# Mergen_Ground_Station_V2_0.net
KiCad netlist of a schematic drawn in EAGLE
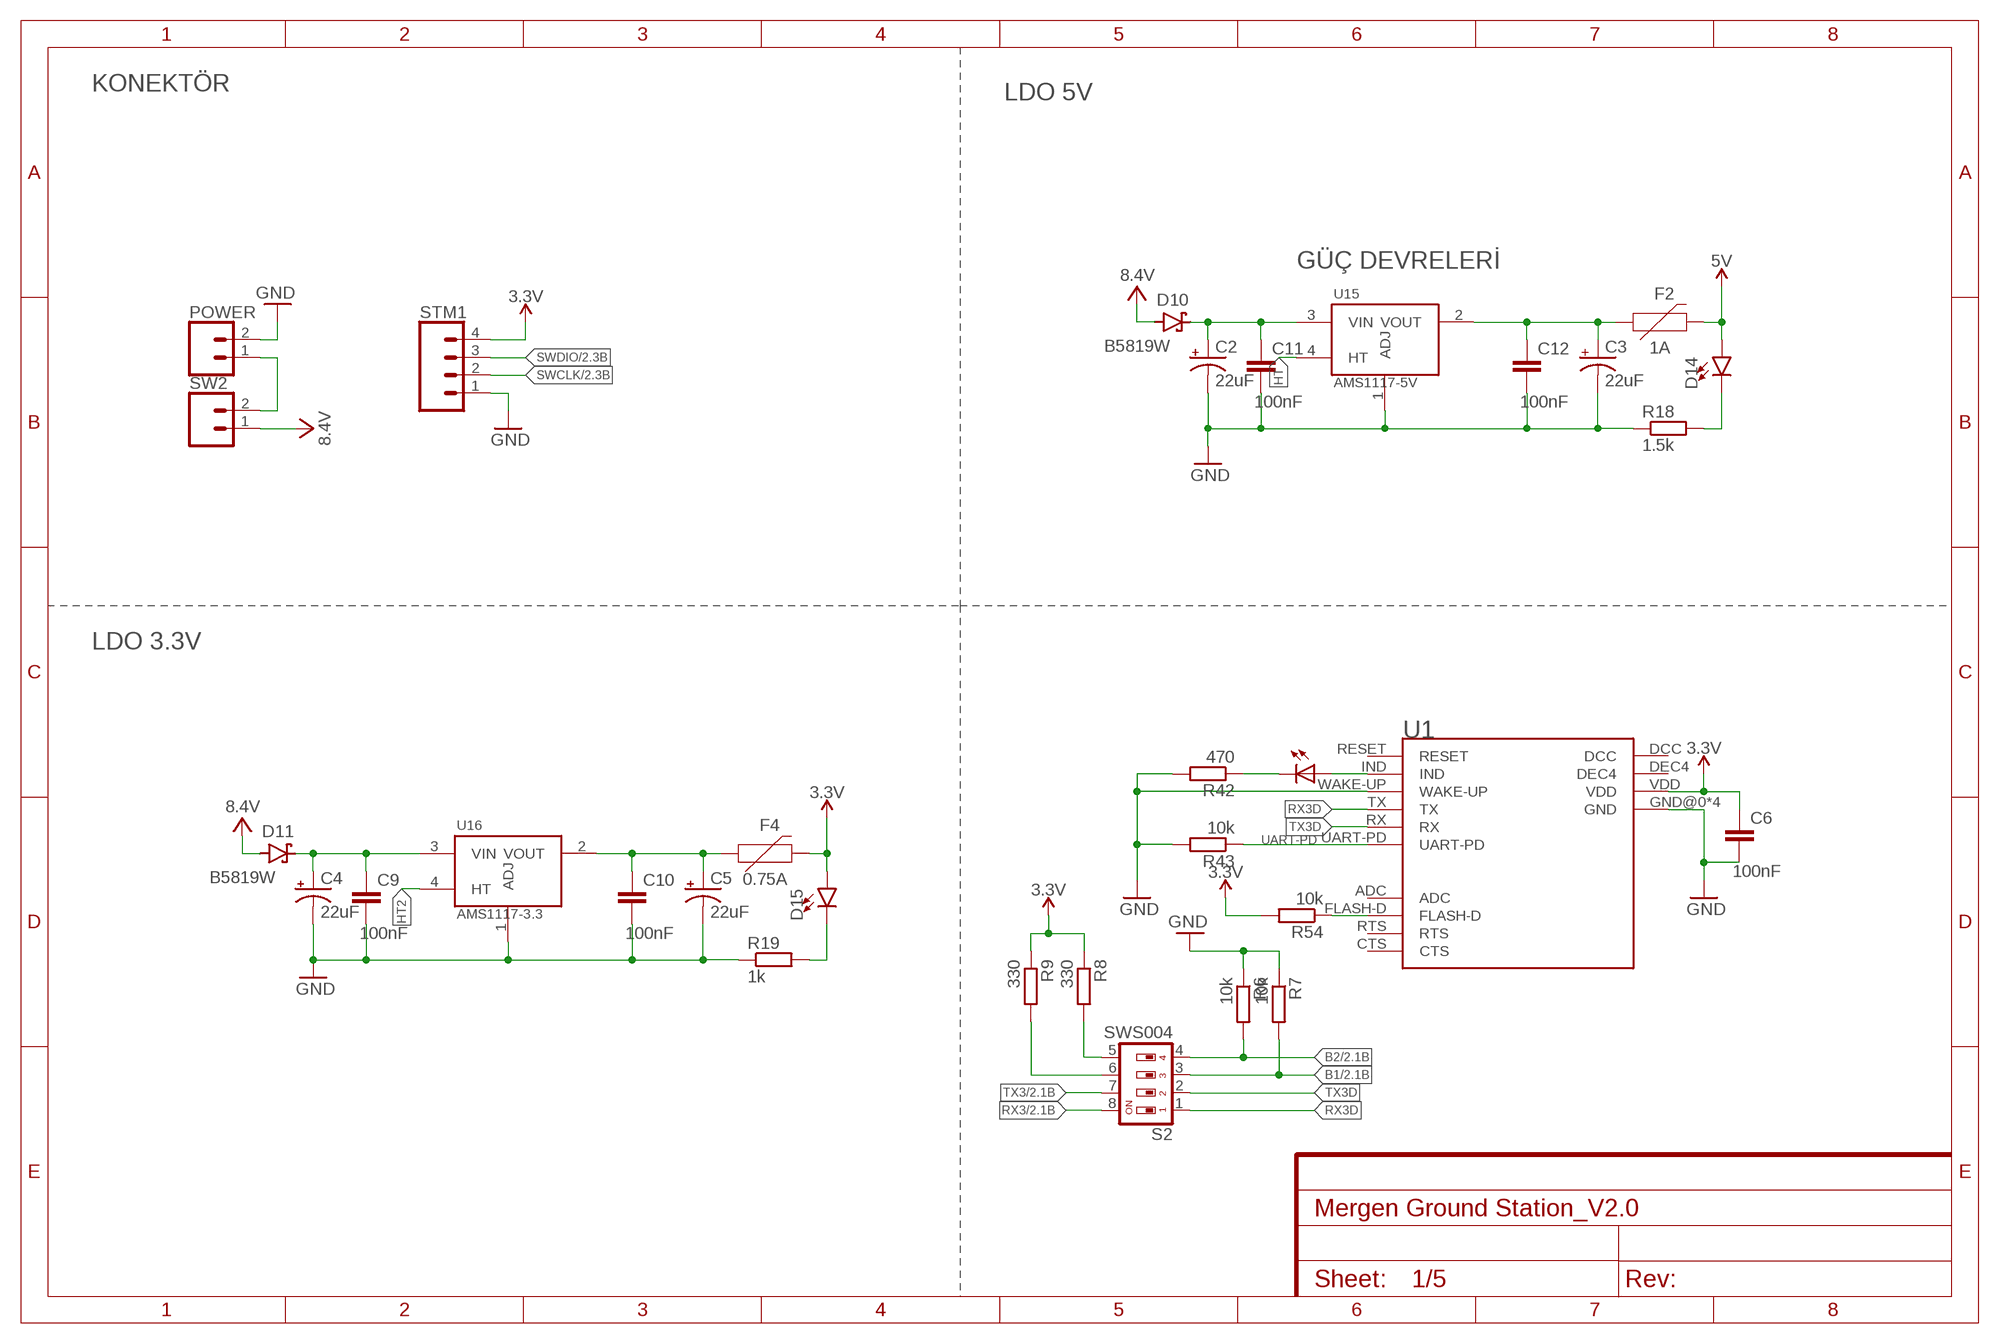
[diagram p0: schematic, sheet 1]
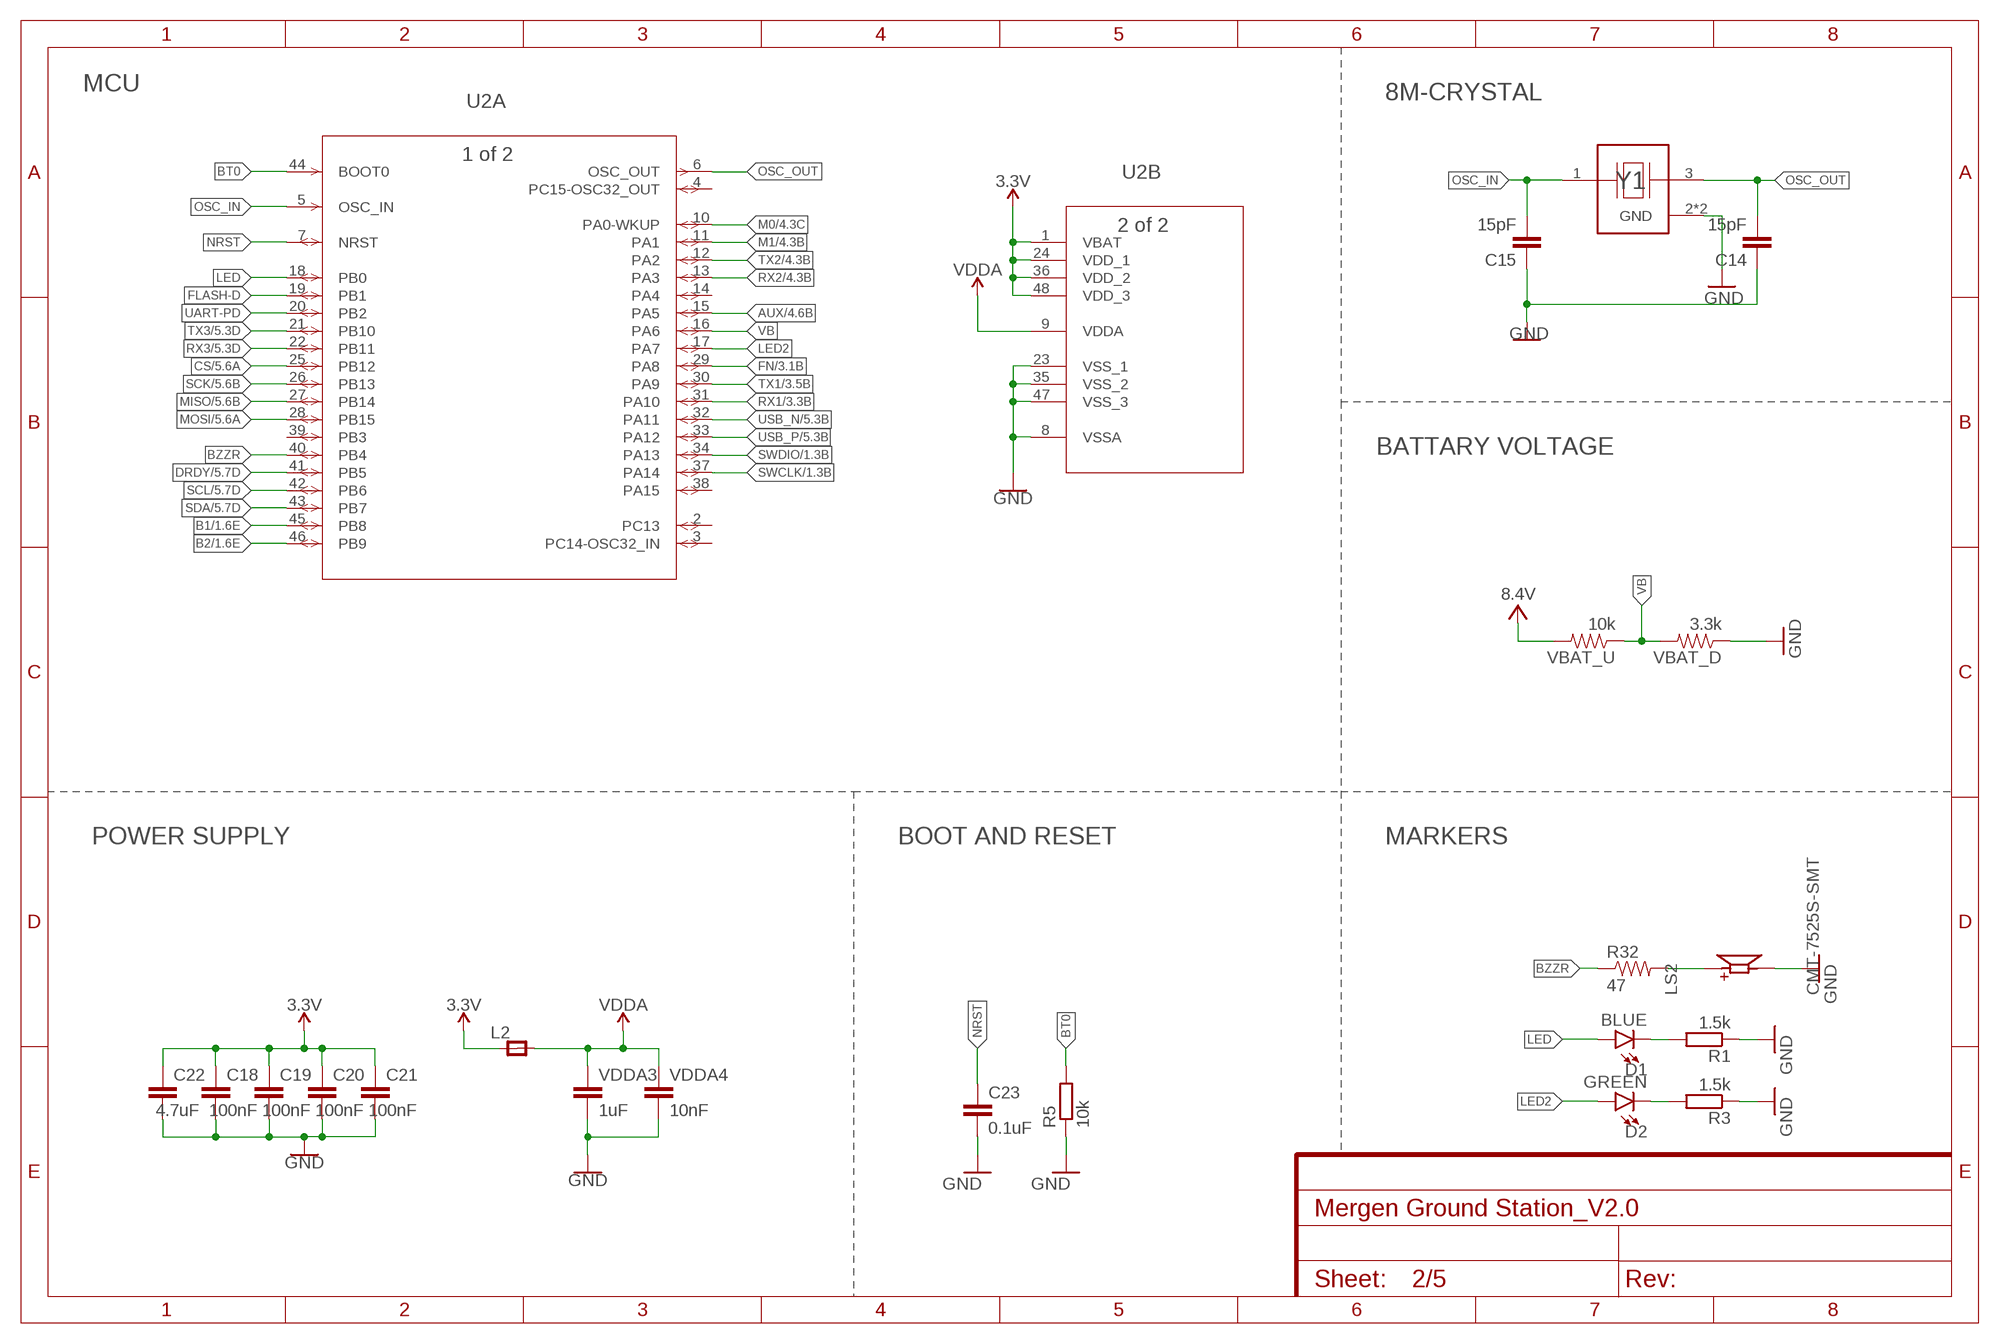
[diagram p1: schematic, sheet 2]
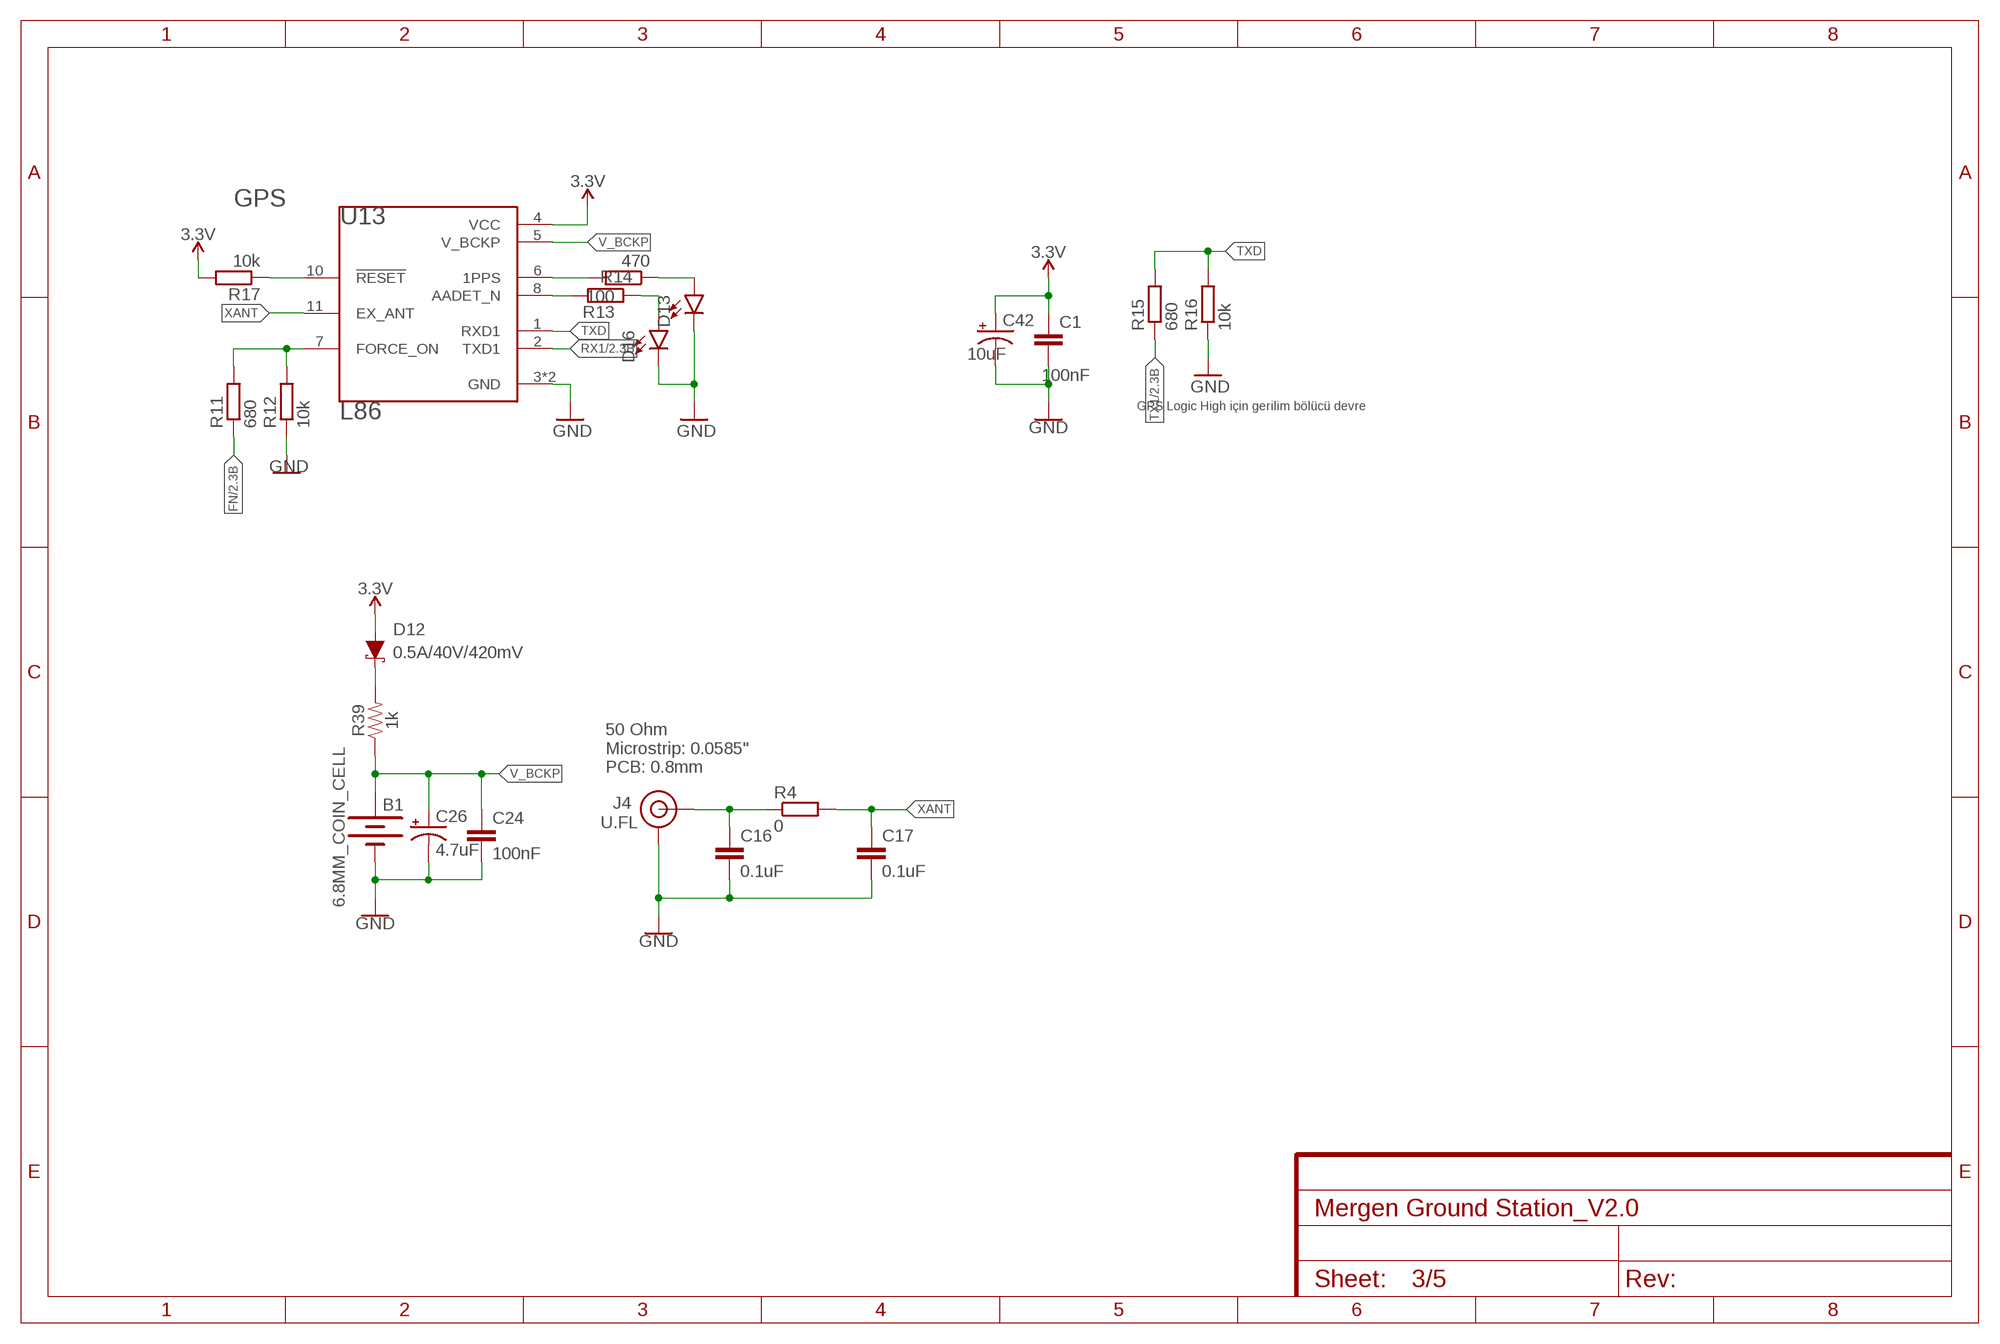
[diagram p2: schematic, sheet 3]
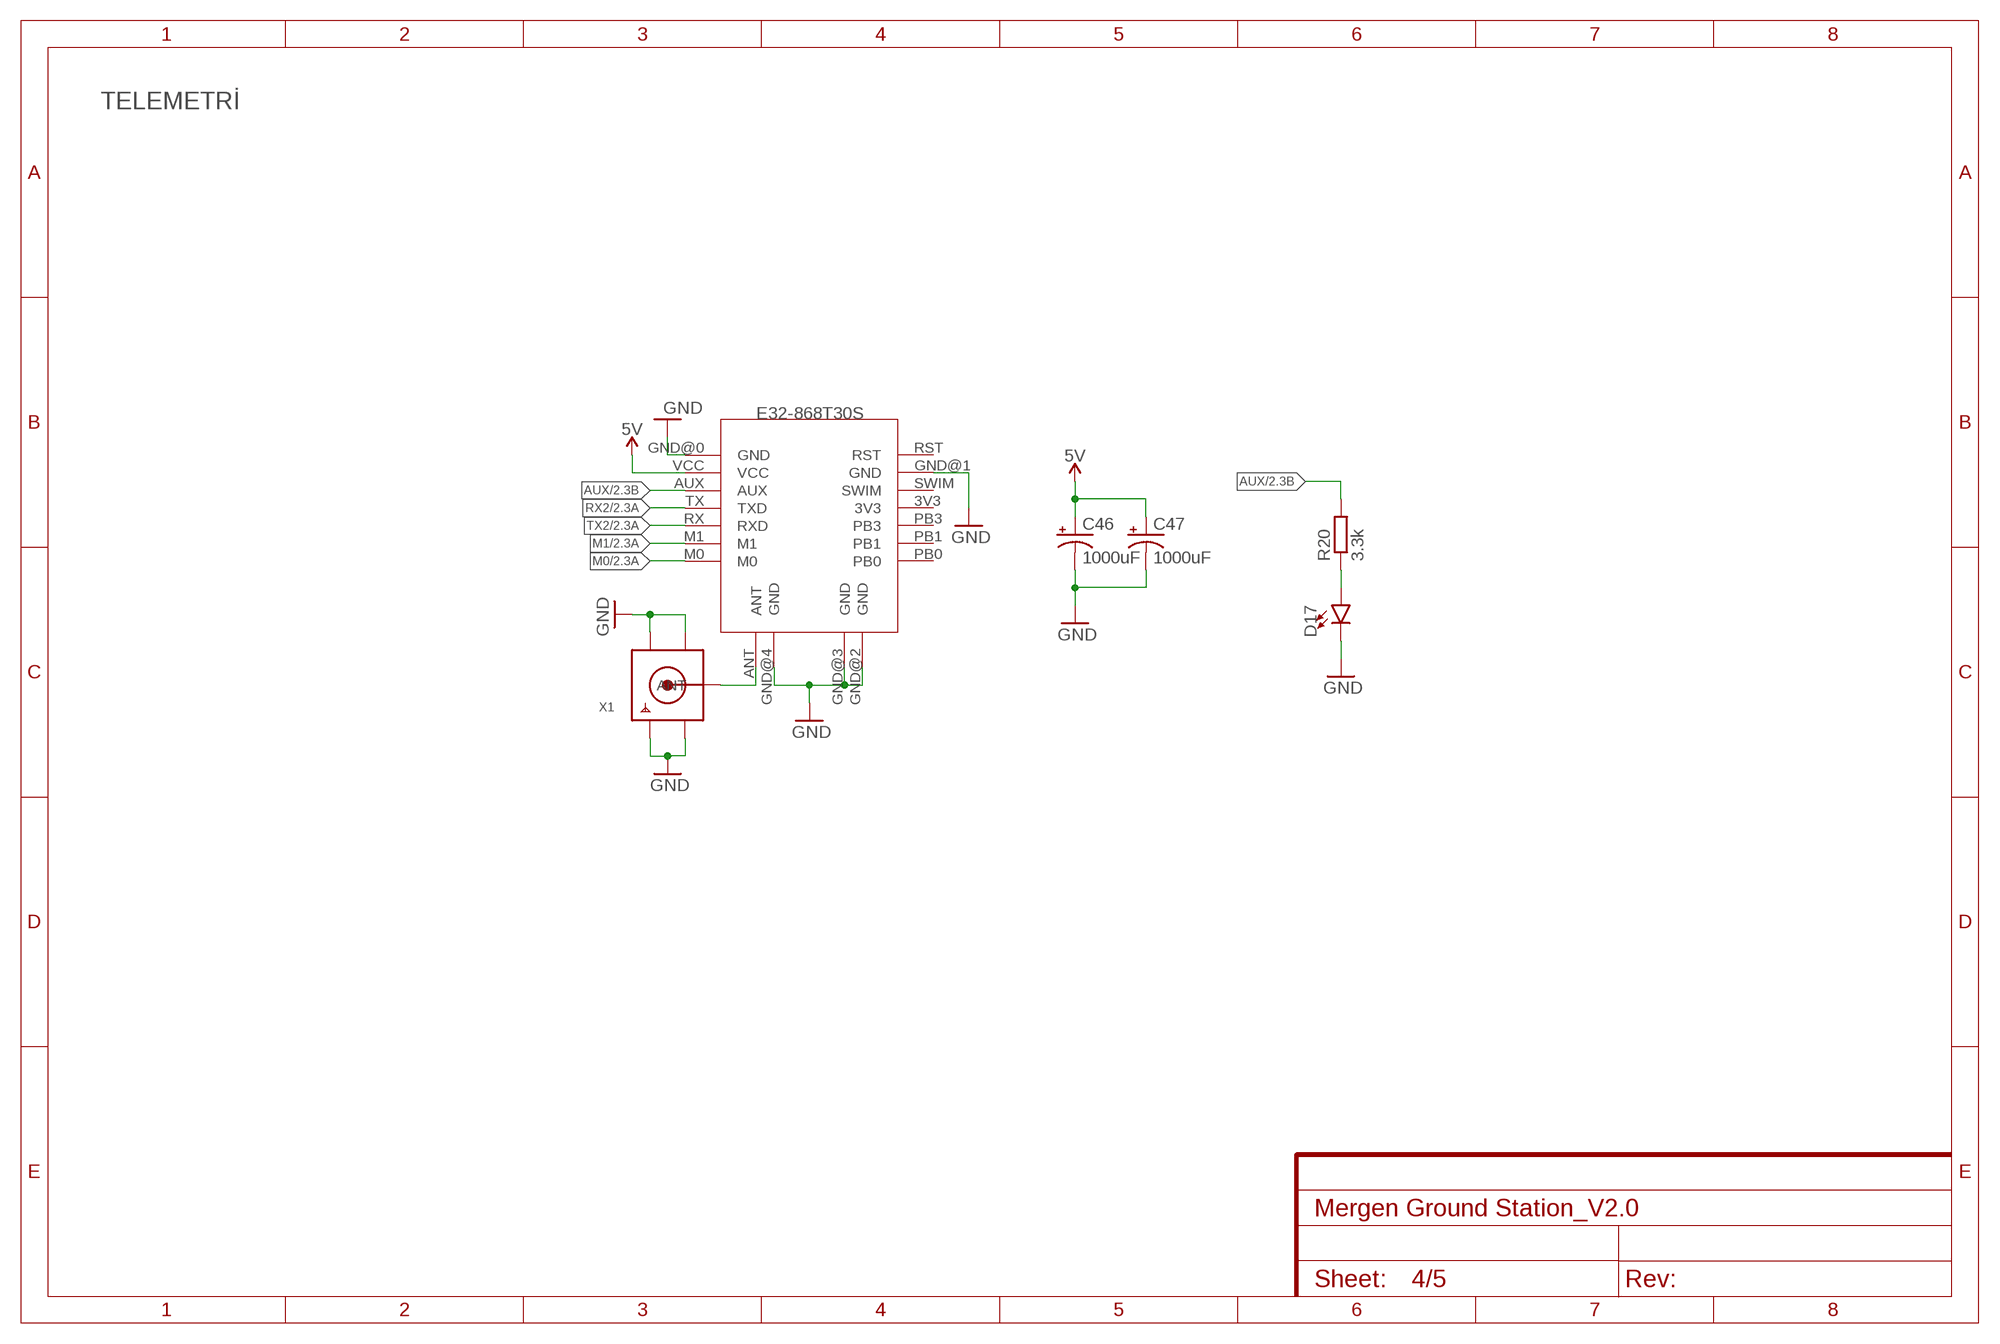
[diagram p3: schematic, sheet 4]
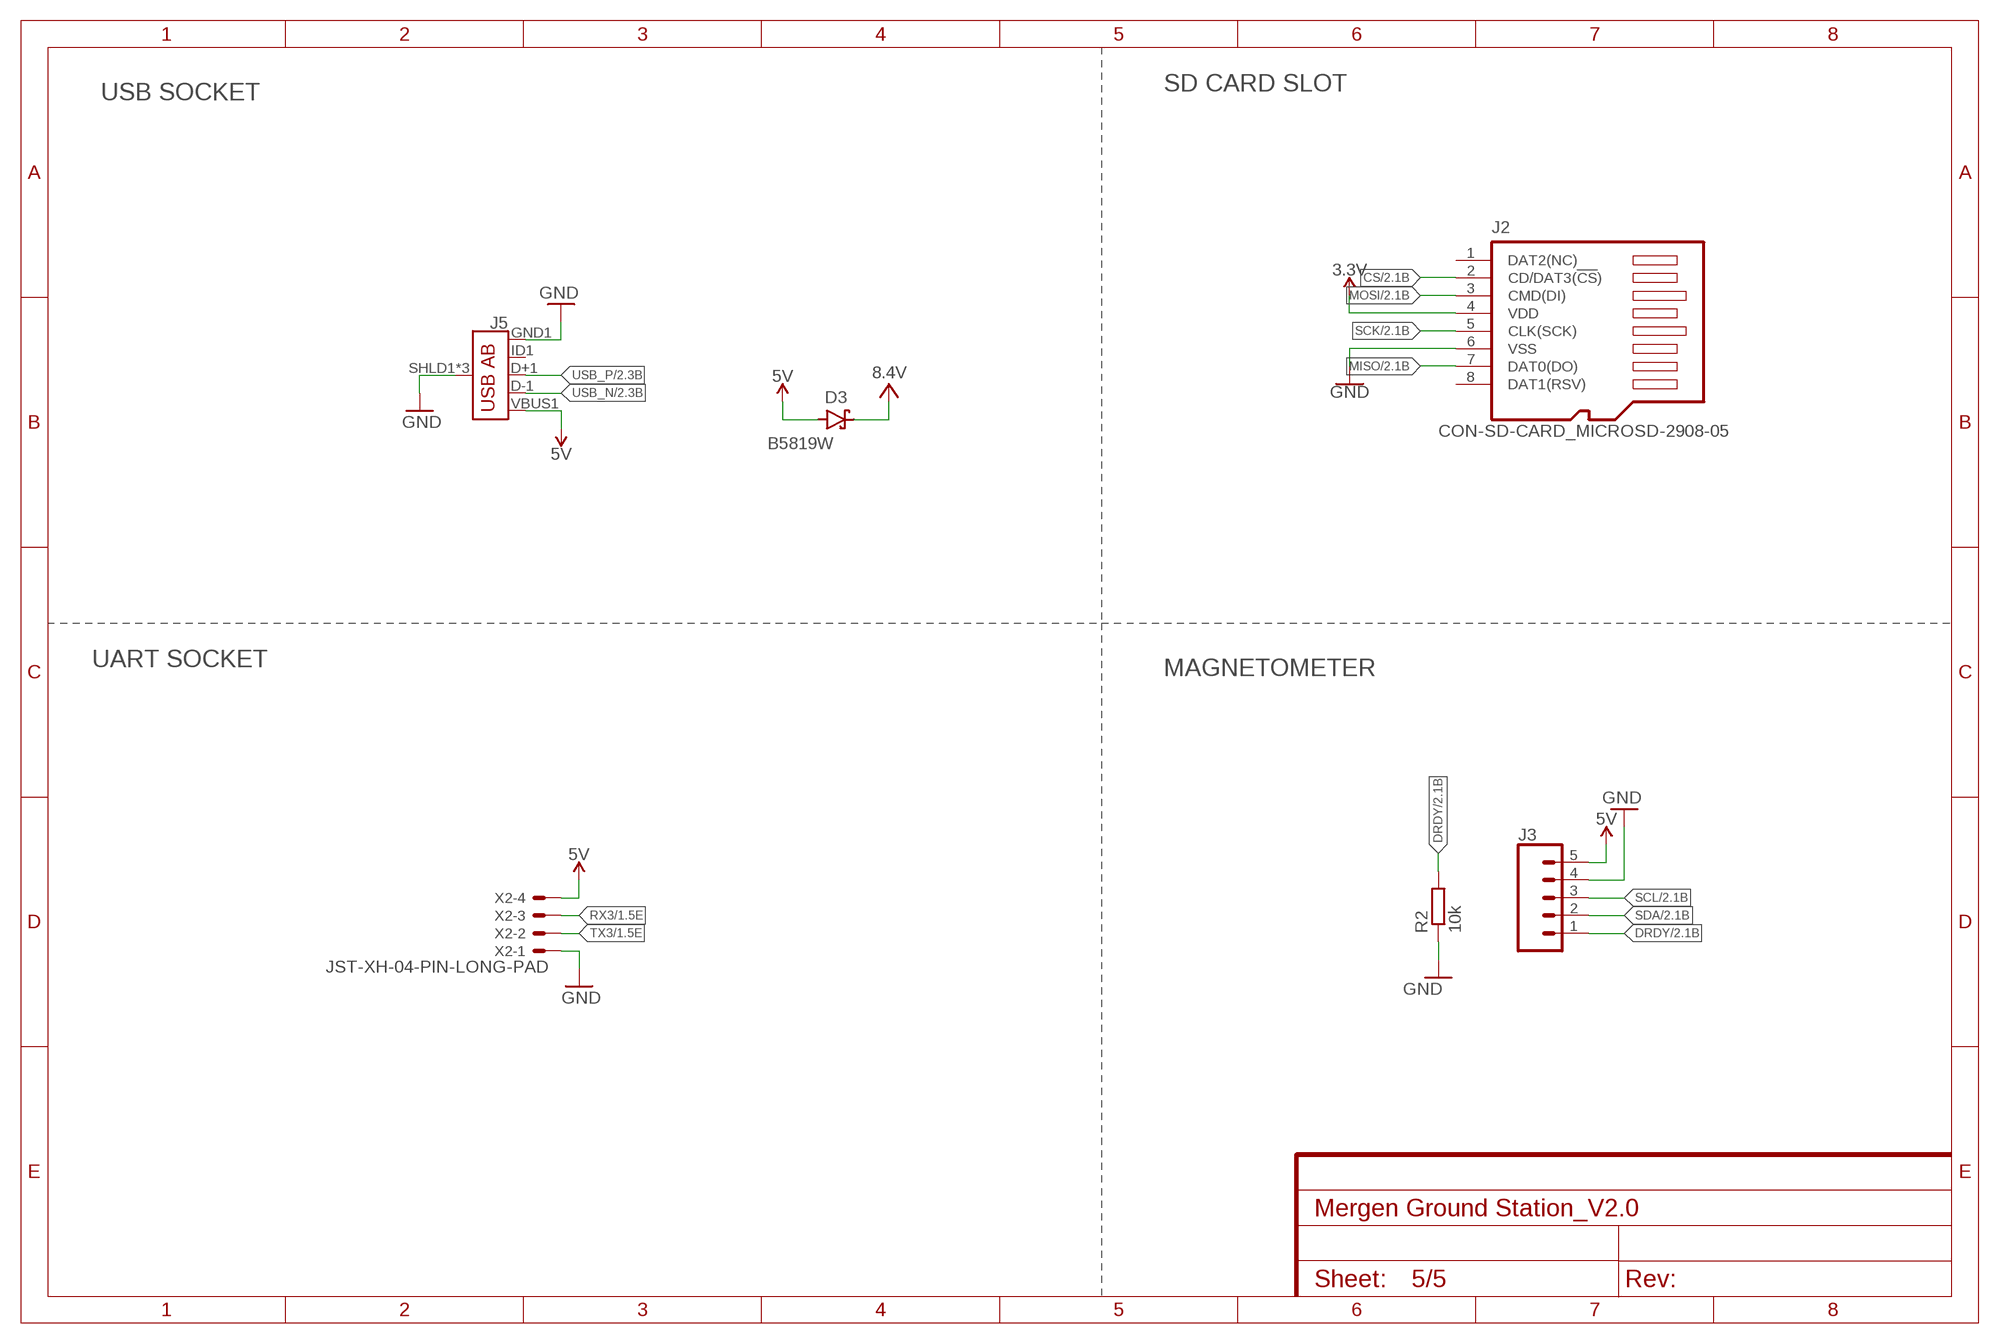
[diagram p4: schematic, sheet 5]

(export (version "E")
  (design (tool "Eeschema 10.0.6"))
  (components
    (comp (ref "C46")
      (value "1000uF")
      (footprint "eagle-import:150CLZ-1010")
      (libsource (lib "eagle-import") (part "CPOL-US150CLZ-1010"))
    )
    (comp (ref "C47")
      (value "1000uF")
      (footprint "eagle-import:150CLZ-1010")
      (libsource (lib "eagle-import") (part "CPOL-US150CLZ-1010"))
    )
    (comp (ref "D17")
      (value "LED0603")
      (footprint "eagle-import:LED-0603")
      (libsource (lib "eagle-import") (part "LED0603"))
    )
    (comp (ref "R20")
      (value "3.3k")
      (footprint "eagle-import:R0603")
      (libsource (lib "eagle-import") (part "rcl_334_R-EU_R0603"))
    )
    (comp (ref "U14")
      (value "E32-868T30S")
      (footprint "eagle-import:E32-868T30S")
      (libsource (lib "eagle-import") (part "E32-868T30S"))
    )
    (comp (ref "X1")
      (value "SMACONNECTOR")
      (footprint "eagle-import:SMA90_DIP")
      (libsource (lib "eagle-import") (part "SMACONNECTOR"))
    )
    (comp (ref "C2")
      (value "22uF")
      (footprint "eagle-import:CT3528")
      (libsource (lib "eagle-import") (part "rcl_334_CPOL-USCT3528"))
    )
    (comp (ref "C3")
      (value "22uF")
      (footprint "eagle-import:CT3528")
      (libsource (lib "eagle-import") (part "rcl_334_CPOL-USCT3528"))
    )
    (comp (ref "C4")
      (value "22uF")
      (footprint "eagle-import:CT3528")
      (libsource (lib "eagle-import") (part "rcl_334_CPOL-USCT3528"))
    )
    (comp (ref "C5")
      (value "22uF")
      (footprint "eagle-import:CT3528")
      (libsource (lib "eagle-import") (part "rcl_334_CPOL-USCT3528"))
    )
    (comp (ref "C6")
      (value "100nF")
      (footprint "eagle-import:C0603")
      (libsource (lib "eagle-import") (part "C-EUC0603"))
    )
    (comp (ref "C9")
      (value "100nF")
      (footprint "eagle-import:C0603")
      (libsource (lib "eagle-import") (part "C-EUC0603"))
    )
    (comp (ref "C10")
      (value "100nF")
      (footprint "eagle-import:C0603")
      (libsource (lib "eagle-import") (part "C-EUC0603"))
    )
    (comp (ref "C11")
      (value "100nF")
      (footprint "eagle-import:C0603")
      (libsource (lib "eagle-import") (part "C-EUC0603"))
    )
    (comp (ref "C12")
      (value "100nF")
      (footprint "eagle-import:C0603")
      (libsource (lib "eagle-import") (part "C-EUC0603"))
    )
    (comp (ref "D10")
      (value "B5819W")
      (footprint "eagle-import:SODFL3718X115")
      (fields (field (name "MANUFACTURER") "ON Semiconductor") (field (name "MPN") "MBR0520LT1G"))
      (libsource (lib "eagle-import") (part "SCHOTTKY_DO-219MBR0520LT1G"))
    )
    (comp (ref "D11")
      (value "B5819W")
      (footprint "eagle-import:SODFL3718X115")
      (fields (field (name "MANUFACTURER") "ON Semiconductor") (field (name "MPN") "MBR0520LT1G"))
      (libsource (lib "eagle-import") (part "SCHOTTKY_DO-219MBR0520LT1G"))
    )
    (comp (ref "D14")
      (value "LED0603")
      (footprint "eagle-import:LED-0603")
      (libsource (lib "eagle-import") (part "LED0603"))
    )
    (comp (ref "D15")
      (value "LED0603")
      (footprint "eagle-import:LED-0603")
      (libsource (lib "eagle-import") (part "LED0603"))
    )
    (comp (ref "DRM3")
      (value "kirmizi")
      (footprint "eagle-import:CHIP-LED0805")
      (libsource (lib "eagle-import") (part "LEDCHIP-LED0805"))
    )
    (comp (ref "F2")
      (value "1A")
      (footprint "eagle-import:1206")
      (libsource (lib "eagle-import") (part "PPTC_HALF-AMP"))
    )
    (comp (ref "F4")
      (value "0.75A")
      (footprint "eagle-import:1206")
      (libsource (lib "eagle-import") (part "PPTC_HALF-AMP"))
    )
    (comp (ref "POWER")
      (value "CONN_023.5MM-NO_SILK")
      (footprint "eagle-import:SCREWTERMINAL-3.5MM-2-NS")
      (libsource (lib "eagle-import") (part "CONN_023.5MM-NO_SILK"))
    )
    (comp (ref "R6")
      (value "10k")
      (footprint "eagle-import:R0603")
      (libsource (lib "eagle-import") (part "R-EU_R0603"))
    )
    (comp (ref "R7")
      (value "10k")
      (footprint "eagle-import:R0603")
      (libsource (lib "eagle-import") (part "R-EU_R0603"))
    )
    (comp (ref "R8")
      (value "330")
      (footprint "eagle-import:R0603")
      (libsource (lib "eagle-import") (part "R-EU_R0603"))
    )
    (comp (ref "R9")
      (value "330")
      (footprint "eagle-import:R0603")
      (libsource (lib "eagle-import") (part "R-EU_R0603"))
    )
    (comp (ref "R18")
      (value "1.5k")
      (footprint "eagle-import:R0603")
      (libsource (lib "eagle-import") (part "rcl_334_R-EU_R0603"))
    )
    (comp (ref "R19")
      (value "1k")
      (footprint "eagle-import:R0603")
      (libsource (lib "eagle-import") (part "rcl_334_R-EU_R0603"))
    )
    (comp (ref "R42")
      (value "470")
      (footprint "eagle-import:R0603")
      (libsource (lib "eagle-import") (part "R-EU_R0603"))
    )
    (comp (ref "R43")
      (value "10k")
      (footprint "eagle-import:R0603")
      (libsource (lib "eagle-import") (part "R-EU_R0603"))
    )
    (comp (ref "R54")
      (value "10k")
      (footprint "eagle-import:R0603")
      (libsource (lib "eagle-import") (part "R-EU_R0603"))
    )
    (comp (ref "S2")
      (value "SWS004")
      (footprint "eagle-import:SMS-004")
      (libsource (lib "eagle-import") (part "SWS004"))
    )
    (comp (ref "STM1")
      (value "CONN_04")
      (footprint "eagle-import:1X04")
      (libsource (lib "eagle-import") (part "CONN_04"))
    )
    (comp (ref "SW2")
      (value "CONN_023.5MM-NO_SILK")
      (footprint "eagle-import:SCREWTERMINAL-3.5MM-2-NS")
      (libsource (lib "eagle-import") (part "CONN_023.5MM-NO_SILK"))
    )
    (comp (ref "U1")
      (value "MDBT42T-AT")
      (footprint "eagle-import:MDBT42T-AT")
      (libsource (lib "eagle-import") (part "MDBT42T-AT"))
    )
    (comp (ref "U15")
      (value "AMS1117-5V")
      (footprint "eagle-import:SOT229P700X180-4N")
      (fields (field (name "MF") "Advanced Monolithic Systems") (field (name "MP") "AMS1117-3.3"))
      (libsource (lib "eagle-import") (part "AMS1117-3.3"))
    )
    (comp (ref "U16")
      (value "AMS1117-3.3")
      (footprint "eagle-import:SOT229P700X180-4N")
      (fields (field (name "MF") "Advanced Monolithic Systems"))
      (libsource (lib "eagle-import") (part "AMS1117-3.3"))
    )
    (comp (ref "D3")
      (value "B5819W")
      (footprint "eagle-import:SODFL3718X115")
      (fields (field (name "MANUFACTURER") "ON Semiconductor") (field (name "MPN") "MBR0520LT1G"))
      (libsource (lib "eagle-import") (part "SCHOTTKY_DO-219MBR0520LT1G"))
    )
    (comp (ref "J2")
      (value "CON-SD-CARD_MICROSD-2908-05")
      (footprint "eagle-import:CON-SD-CARD_2908-05")
      (libsource (lib "eagle-import") (part "CON-SD-CARD_MICROSD-2908-05"))
    )
    (comp (ref "J3")
      (value "CONN_05LOCK_LONGPADS")
      (footprint "eagle-import:1X05_LOCK_LONGPADS")
      (libsource (lib "eagle-import") (part "CONN_05LOCK_LONGPADS"))
    )
    (comp (ref "J5")
      (value "USB_AB_SMT")
      (footprint "eagle-import:USB-AB-MICRO-SMD")
      (libsource (lib "eagle-import") (part "USB_AB_SMT"))
    )
    (comp (ref "R2")
      (value "10k")
      (footprint "eagle-import:R0603")
      (libsource (lib "eagle-import") (part "rcl_334_R-EU_R0603"))
    )
    (comp (ref "X2")
      (value "JST-XH-04-PIN-LONG-PAD")
      (footprint "eagle-import:JST-XH-04-PACKAGE-LONG-PAD")
      (libsource (lib "eagle-import") (part "JST-XH-04-PIN-LONG-PAD"))
    )
    (comp (ref "C14")
      (value "15pF")
      (footprint "eagle-import:C0603")
      (libsource (lib "eagle-import") (part "C-EUC0603"))
    )
    (comp (ref "C15")
      (value "15pF")
      (footprint "eagle-import:C0603")
      (libsource (lib "eagle-import") (part "C-EUC0603"))
    )
    (comp (ref "C18")
      (value "100nF")
      (footprint "eagle-import:C0603")
      (libsource (lib "eagle-import") (part "C-EUC0603"))
    )
    (comp (ref "C19")
      (value "100nF")
      (footprint "eagle-import:C0603")
      (libsource (lib "eagle-import") (part "C-EUC0603"))
    )
    (comp (ref "C20")
      (value "100nF")
      (footprint "eagle-import:C0603")
      (libsource (lib "eagle-import") (part "C-EUC0603"))
    )
    (comp (ref "C21")
      (value "100nF")
      (footprint "eagle-import:C0603")
      (libsource (lib "eagle-import") (part "C-EUC0603"))
    )
    (comp (ref "C22")
      (value "4.7uF")
      (footprint "eagle-import:C0603")
      (libsource (lib "eagle-import") (part "C-EUC0603"))
    )
    (comp (ref "C23")
      (value "0.1uF")
      (footprint "eagle-import:C0603")
      (libsource (lib "eagle-import") (part "C-EUC0603"))
    )
    (comp (ref "D1")
      (value "BLUE")
      (footprint "eagle-import:LED-0603")
      (libsource (lib "eagle-import") (part "LED0603"))
    )
    (comp (ref "D2")
      (value "GREEN")
      (footprint "eagle-import:LED-0603")
      (libsource (lib "eagle-import") (part "LED0603"))
    )
    (comp (ref "L2")
      (value "RC-MASTER-SMD_FB_0805MP")
      (footprint "eagle-import:RC-MASTER-SMD_L0805MP")
      (libsource (lib "eagle-import") (part "RC-MASTER-SMD_FB_0805MP"))
    )
    (comp (ref "LS2")
      (value "CMT-7525S-SMT")
      (footprint "eagle-import:CUI_CMT-7525S-SMT")
      (fields (field (name "MF") "CUI Devices") (field (name "MP") "CMT-7525S-SMT-TR"))
      (libsource (lib "eagle-import") (part "CMT-7525S-SMT"))
    )
    (comp (ref "R1")
      (value "1.5k")
      (footprint "eagle-import:R0603")
      (libsource (lib "eagle-import") (part "rcl_334_R-EU_R0603"))
    )
    (comp (ref "R3")
      (value "1.5k")
      (footprint "eagle-import:R0603")
      (libsource (lib "eagle-import") (part "rcl_334_R-EU_R0603"))
    )
    (comp (ref "R5")
      (value "10k")
      (footprint "eagle-import:R0603")
      (libsource (lib "eagle-import") (part "rcl_334_R-EU_R0603"))
    )
    (comp (ref "R32")
      (value "47")
      (footprint "eagle-import:0603")
      (libsource (lib "eagle-import") (part "0OHM-0603-1/10W-5%"))
    )
    (comp (ref "U2")
      (value "STM32F103C8T6")
      (footprint "eagle-import:LQFP48-7X7MM")
      (fields (field (name "COPYRIGHT") "Copyright (C) 2018 Accelerated Designs. All rights reserved"))
      (libsource (lib "eagle-import") (part "STM32F103C8T6"))
    )
    (comp (ref "VBAT_D")
      (value "3.3k")
      (footprint "eagle-import:0603-RES")
      (libsource (lib "eagle-import") (part "2.0KOHM1/10W5%(0603)"))
    )
    (comp (ref "VBAT_U")
      (value "10k")
      (footprint "eagle-import:0603-RES")
      (libsource (lib "eagle-import") (part "2.0KOHM1/10W5%(0603)"))
    )
    (comp (ref "VDDA3")
      (value "1uF")
      (footprint "eagle-import:0603")
      (libsource (lib "eagle-import") (part "0.1UF-0603-25V-(+80/-20%)"))
    )
    (comp (ref "VDDA4")
      (value "10nF")
      (footprint "eagle-import:0603")
      (libsource (lib "eagle-import") (part "0.1UF-0603-25V-(+80/-20%)"))
    )
    (comp (ref "Y1")
      (value "ABMM2-8.000MHZ-E2-T")
      (footprint "eagle-import:XTAL_ABMM2-8.000MHZ-E2-T")
      (fields (field (name "MF") "Abracon"))
      (libsource (lib "eagle-import") (part "ABMM2-8.000MHZ-E2-T"))
    )
    (comp (ref "B1")
      (value "6.8MM_COIN_CELL")
      (footprint "eagle-import:BATTCON-6.8MM")
      (libsource (lib "eagle-import") (part "BATTERY-6.8MM_SMD"))
    )
    (comp (ref "C1")
      (value "100nF")
      (footprint "eagle-import:C0603")
      (libsource (lib "eagle-import") (part "C-EUC0603"))
    )
    (comp (ref "C16")
      (value "0.1uF")
      (footprint "eagle-import:C0603")
      (libsource (lib "eagle-import") (part "C-EUC0603"))
    )
    (comp (ref "C17")
      (value "0.1uF")
      (footprint "eagle-import:C0603")
      (libsource (lib "eagle-import") (part "C-EUC0603"))
    )
    (comp (ref "C24")
      (value "100nF")
      (footprint "eagle-import:C0603")
      (libsource (lib "eagle-import") (part "C-EUC0603"))
    )
    (comp (ref "C26")
      (value "4.7uF")
      (footprint "eagle-import:A_3216-18R")
      (libsource (lib "eagle-import") (part "rcl_334_CPOL-USA/3216-18R"))
    )
    (comp (ref "C42")
      (value "10uF")
      (footprint "eagle-import:EIA3216")
      (libsource (lib "eagle-import") (part "10UF-POLAR-EIA3216-16V-10%(TANT)"))
    )
    (comp (ref "D12")
      (value "0.5A/40V/420mV")
      (footprint "eagle-import:SOD-323")
      (libsource (lib "eagle-import") (part "DIODE-SCHOTTKY-PMEG4005EJ"))
    )
    (comp (ref "D13")
      (value "LED0603")
      (footprint "eagle-import:LED-0603")
      (libsource (lib "eagle-import") (part "LED0603"))
    )
    (comp (ref "D16")
      (value "LED0603")
      (footprint "eagle-import:LED-0603")
      (libsource (lib "eagle-import") (part "LED0603"))
    )
    (comp (ref "J4")
      (value "U.FL")
      (footprint "eagle-import:U.FL")
      (libsource (lib "eagle-import") (part "U.FL2PIN"))
    )
    (comp (ref "R4")
      (value "0")
      (footprint "eagle-import:R0603")
      (libsource (lib "eagle-import") (part "rcl_334_R-EU_R0603"))
    )
    (comp (ref "R11")
      (value "680")
      (footprint "eagle-import:R0603")
      (libsource (lib "eagle-import") (part "rcl_334_R-EU_R0603"))
    )
    (comp (ref "R12")
      (value "10k")
      (footprint "eagle-import:R0603")
      (libsource (lib "eagle-import") (part "rcl_334_R-EU_R0603"))
    )
    (comp (ref "R13")
      (value "100")
      (footprint "eagle-import:R0603")
      (libsource (lib "eagle-import") (part "rcl_334_R-EU_R0603"))
    )
    (comp (ref "R14")
      (value "470")
      (footprint "eagle-import:R0603")
      (libsource (lib "eagle-import") (part "rcl_334_R-EU_R0603"))
    )
    (comp (ref "R15")
      (value "680")
      (footprint "eagle-import:R0603")
      (libsource (lib "eagle-import") (part "rcl_334_R-EU_R0603"))
    )
    (comp (ref "R16")
      (value "10k")
      (footprint "eagle-import:R0603")
      (libsource (lib "eagle-import") (part "rcl_334_R-EU_R0603"))
    )
    (comp (ref "R17")
      (value "10k")
      (footprint "eagle-import:R0603")
      (libsource (lib "eagle-import") (part "rcl_334_R-EU_R0603"))
    )
    (comp (ref "R39")
      (value "1k")
      (footprint "eagle-import:0603")
      (libsource (lib "eagle-import") (part "1KOHM-0603-1/10W-1%"))
    )
    (comp (ref "U13")
      (value "L86")
      (footprint "eagle-import:XCVR_L86")
      (fields (field (name "MF") "Quectel"))
      (libsource (lib "eagle-import") (part "L86"))
    )
  )
  (nets
    (net (code "1") (name "3.3V") (class "Default")
      (node (ref "C1") (pin "1") (pinfunction "1_1") (pintype "passive"))
      (node (ref "C18") (pin "1") (pinfunction "1_1") (pintype "passive"))
      (node (ref "C19") (pin "1") (pinfunction "1_1") (pintype "passive"))
      (node (ref "C20") (pin "1") (pinfunction "1_1") (pintype "passive"))
      (node (ref "C21") (pin "1") (pinfunction "1_1") (pintype "passive"))
      (node (ref "C22") (pin "1") (pinfunction "1_1") (pintype "passive"))
      (node (ref "C42") (pin "+") (pinfunction "+_+") (pintype "passive"))
      (node (ref "C6") (pin "1") (pinfunction "1_1") (pintype "passive"))
      (node (ref "D12") (pin "A") (pinfunction "A_A") (pintype "passive"))
      (node (ref "D15") (pin "A") (pinfunction "A_A") (pintype "passive"))
      (node (ref "F4") (pin "2") (pinfunction "2_2") (pintype "bidirectional"))
      (node (ref "J2") (pin "4") (pinfunction "VDD_4") (pintype "bidirectional"))
      (node (ref "L2") (pin "1") (pinfunction "1_1") (pintype "passive"))
      (node (ref "R17") (pin "2") (pinfunction "2_2") (pintype "passive"))
      (node (ref "R54") (pin "2") (pinfunction "2_2") (pintype "passive"))
      (node (ref "R8") (pin "1") (pinfunction "1_1") (pintype "passive"))
      (node (ref "R9") (pin "1") (pinfunction "1_1") (pintype "passive"))
      (node (ref "STM1") (pin "4") (pinfunction "4_4") (pintype "passive"))
      (node (ref "U1") (pin "VDD") (pinfunction "VDD_VDD") (pintype "bidirectional"))
      (node (ref "U13") (pin "4") (pinfunction "VCC_4") (pintype "power_in"))
      (node (ref "U2") (pin "1") (pinfunction "VBAT_1") (pintype "power_in"))
      (node (ref "U2") (pin "24") (pinfunction "VDD_1_24") (pintype "power_in"))
      (node (ref "U2") (pin "36") (pinfunction "VDD_2_36") (pintype "power_in"))
      (node (ref "U2") (pin "48") (pinfunction "VDD_3_48") (pintype "power_in"))
    )
    (net (code "2") (name "5V") (class "Default")
      (node (ref "C46") (pin "+") (pinfunction "+_+") (pintype "passive"))
      (node (ref "C47") (pin "+") (pinfunction "+_+") (pintype "passive"))
      (node (ref "D14") (pin "A") (pinfunction "A_A") (pintype "passive"))
      (node (ref "D3") (pin "2") (pinfunction "A_2") (pintype "passive"))
      (node (ref "F2") (pin "2") (pinfunction "2_2") (pintype "bidirectional"))
      (node (ref "J3") (pin "5") (pinfunction "5_5") (pintype "passive"))
      (node (ref "J5") (pin "VBUS1") (pinfunction "VBUS_VBUS1") (pintype "power_in"))
      (node (ref "U14") (pin "VCC") (pinfunction "VCC_VCC") (pintype "bidirectional"))
      (node (ref "X2") (pin "4") (pinfunction "S_4") (pintype "passive"))
    )
    (net (code "3") (name "AUX") (class "Default")
      (node (ref "R20") (pin "2") (pinfunction "2_2") (pintype "passive"))
      (node (ref "U14") (pin "AUX") (pinfunction "AUX_AUX") (pintype "bidirectional"))
      (node (ref "U2") (pin "15") (pinfunction "PA5_15") (pintype "bidirectional"))
    )
    (net (code "4") (name "B1") (class "Default")
      (node (ref "R7") (pin "2") (pinfunction "2_2") (pintype "passive"))
      (node (ref "S2") (pin "3") (pinfunction "3_3") (pintype "passive"))
      (node (ref "U2") (pin "45") (pinfunction "PB8_45") (pintype "bidirectional"))
    )
    (net (code "5") (name "B2") (class "Default")
      (node (ref "R6") (pin "2") (pinfunction "2_2") (pintype "passive"))
      (node (ref "S2") (pin "4") (pinfunction "4_4") (pintype "passive"))
      (node (ref "U2") (pin "46") (pinfunction "PB9_46") (pintype "bidirectional"))
    )
    (net (code "6") (name "BT0") (class "Default")
      (node (ref "R5") (pin "2") (pinfunction "2_2") (pintype "passive"))
      (node (ref "U2") (pin "44") (pinfunction "BOOT0_44") (pintype "input"))
    )
    (net (code "7") (name "BZZR") (class "Default")
      (node (ref "R32") (pin "1") (pinfunction "1_1") (pintype "passive"))
      (node (ref "U2") (pin "40") (pinfunction "PB4_40") (pintype "bidirectional"))
    )
    (net (code "8") (name "CS") (class "Default")
      (node (ref "J2") (pin "2") (pinfunction "CD/DAT3(~{CS})_2") (pintype "bidirectional"))
      (node (ref "U2") (pin "25") (pinfunction "PB12_25") (pintype "bidirectional"))
    )
    (net (code "9") (name "DRDY") (class "Default")
      (node (ref "J3") (pin "1") (pinfunction "1_1") (pintype "passive"))
      (node (ref "R2") (pin "2") (pinfunction "2_2") (pintype "passive"))
      (node (ref "U2") (pin "41") (pinfunction "PB5_41") (pintype "bidirectional"))
    )
    (net (code "10") (name "FLASH-D") (class "Default")
      (node (ref "R54") (pin "1") (pinfunction "1_1") (pintype "passive"))
      (node (ref "U1") (pin "FLASH-D") (pinfunction "FLASH-D_FLASH-D") (pintype "bidirectional"))
      (node (ref "U2") (pin "19") (pinfunction "PB1_19") (pintype "bidirectional"))
    )
    (net (code "11") (name "FN") (class "Default")
      (node (ref "R11") (pin "1") (pinfunction "1_1") (pintype "passive"))
      (node (ref "U2") (pin "29") (pinfunction "PA8_29") (pintype "bidirectional"))
    )
    (net (code "12") (name "GND") (class "Default")
      (node (ref "B1") (pin "-") (pinfunction "-_-") (pintype "power_in"))
      (node (ref "C1") (pin "2") (pinfunction "2_2") (pintype "passive"))
      (node (ref "C10") (pin "2") (pinfunction "2_2") (pintype "passive"))
      (node (ref "C11") (pin "2") (pinfunction "2_2") (pintype "passive"))
      (node (ref "C12") (pin "2") (pinfunction "2_2") (pintype "passive"))
      (node (ref "C14") (pin "1") (pinfunction "1_1") (pintype "passive"))
      (node (ref "C15") (pin "1") (pinfunction "1_1") (pintype "passive"))
      (node (ref "C16") (pin "2") (pinfunction "2_2") (pintype "passive"))
      (node (ref "C17") (pin "2") (pinfunction "2_2") (pintype "passive"))
      (node (ref "C18") (pin "2") (pinfunction "2_2") (pintype "passive"))
      (node (ref "C19") (pin "2") (pinfunction "2_2") (pintype "passive"))
      (node (ref "C2") (pin "-") (pinfunction "-_-") (pintype "passive"))
      (node (ref "C20") (pin "2") (pinfunction "2_2") (pintype "passive"))
      (node (ref "C21") (pin "2") (pinfunction "2_2") (pintype "passive"))
      (node (ref "C22") (pin "2") (pinfunction "2_2") (pintype "passive"))
      (node (ref "C23") (pin "2") (pinfunction "2_2") (pintype "passive"))
      (node (ref "C24") (pin "2") (pinfunction "2_2") (pintype "passive"))
      (node (ref "C26") (pin "-") (pinfunction "-_-") (pintype "passive"))
      (node (ref "C3") (pin "-") (pinfunction "-_-") (pintype "passive"))
      (node (ref "C4") (pin "-") (pinfunction "-_-") (pintype "passive"))
      (node (ref "C42") (pin "-") (pinfunction "-_-") (pintype "passive"))
      (node (ref "C46") (pin "-") (pinfunction "-_-") (pintype "passive"))
      (node (ref "C47") (pin "-") (pinfunction "-_-") (pintype "passive"))
      (node (ref "C5") (pin "-") (pinfunction "-_-") (pintype "passive"))
      (node (ref "C6") (pin "2") (pinfunction "2_2") (pintype "passive"))
      (node (ref "C9") (pin "2") (pinfunction "2_2") (pintype "passive"))
      (node (ref "D13") (pin "C") (pinfunction "C_C") (pintype "passive"))
      (node (ref "D16") (pin "C") (pinfunction "C_C") (pintype "passive"))
      (node (ref "D17") (pin "C") (pinfunction "C_C") (pintype "passive"))
      (node (ref "J2") (pin "6") (pinfunction "VSS_6") (pintype "bidirectional"))
      (node (ref "J3") (pin "4") (pinfunction "4_4") (pintype "passive"))
      (node (ref "J4") (pin "1") (pinfunction "GND_1") (pintype "bidirectional"))
      (node (ref "J4") (pin "2") (pinfunction "GND_2") (pintype "bidirectional"))
      (node (ref "J5") (pin "GND1") (pinfunction "GND_GND1") (pintype "power_in"))
      (node (ref "J5") (pin "SHLD1") (pinfunction "SHIELD_SHLD1") (pintype "bidirectional"))
      (node (ref "J5") (pin "SHLD2") (pinfunction "SHIELD_SHLD2") (pintype "bidirectional"))
      (node (ref "J5") (pin "SHLD3") (pinfunction "SHIELD_SHLD3") (pintype "bidirectional"))
      (node (ref "LS2") (pin "N") (pinfunction "N_N") (pintype "passive"))
      (node (ref "POWER") (pin "2") (pinfunction "2_2") (pintype "passive"))
      (node (ref "R1") (pin "1") (pinfunction "1_1") (pintype "passive"))
      (node (ref "R12") (pin "1") (pinfunction "1_1") (pintype "passive"))
      (node (ref "R16") (pin "1") (pinfunction "1_1") (pintype "passive"))
      (node (ref "R18") (pin "1") (pinfunction "1_1") (pintype "passive"))
      (node (ref "R19") (pin "1") (pinfunction "1_1") (pintype "passive"))
      (node (ref "R2") (pin "1") (pinfunction "1_1") (pintype "passive"))
      (node (ref "R3") (pin "1") (pinfunction "1_1") (pintype "passive"))
      (node (ref "R42") (pin "2") (pinfunction "2_2") (pintype "passive"))
      (node (ref "R43") (pin "2") (pinfunction "2_2") (pintype "passive"))
      (node (ref "R5") (pin "1") (pinfunction "1_1") (pintype "passive"))
      (node (ref "R6") (pin "1") (pinfunction "1_1") (pintype "passive"))
      (node (ref "R7") (pin "1") (pinfunction "1_1") (pintype "passive"))
      (node (ref "STM1") (pin "1") (pinfunction "1_1") (pintype "passive"))
      (node (ref "U1") (pin "GND@0") (pinfunction "GND_GND@0") (pintype "bidirectional"))
      (node (ref "U1") (pin "GND@1") (pinfunction "GND_GND@1") (pintype "bidirectional"))
      (node (ref "U1") (pin "GND@2") (pinfunction "GND_GND@2") (pintype "bidirectional"))
      (node (ref "U1") (pin "GND@3") (pinfunction "GND_GND@3") (pintype "bidirectional"))
      (node (ref "U1") (pin "WAKE-UP") (pinfunction "WAKE-UP_WAKE-UP") (pintype "bidirectional"))
      (node (ref "U13") (pin "12") (pinfunction "GND_12") (pintype "passive"))
      (node (ref "U13") (pin "3") (pinfunction "GND_3") (pintype "passive"))
      (node (ref "U14") (pin "GND@0") (pinfunction "GND_GND@0") (pintype "bidirectional"))
      (node (ref "U14") (pin "GND@1") (pinfunction "GND_GND@1") (pintype "bidirectional"))
      (node (ref "U14") (pin "GND@2") (pinfunction "GND_GND@2") (pintype "bidirectional"))
      (node (ref "U14") (pin "GND@3") (pinfunction "GND_GND@3") (pintype "bidirectional"))
      (node (ref "U14") (pin "GND@4") (pinfunction "GND_GND@4") (pintype "bidirectional"))
      (node (ref "U15") (pin "1") (pinfunction "ADJ_1") (pintype "power_in"))
      (node (ref "U16") (pin "1") (pinfunction "ADJ_1") (pintype "power_in"))
      (node (ref "U2") (pin "23") (pinfunction "VSS_1_23") (pintype "power_in"))
      (node (ref "U2") (pin "35") (pinfunction "VSS_2_35") (pintype "power_in"))
      (node (ref "U2") (pin "47") (pinfunction "VSS_3_47") (pintype "power_in"))
      (node (ref "U2") (pin "8") (pinfunction "VSSA_8") (pintype "power_in"))
      (node (ref "VBAT_D") (pin "1") (pinfunction "1_1") (pintype "passive"))
      (node (ref "VDDA3") (pin "2") (pinfunction "2_2") (pintype "passive"))
      (node (ref "VDDA4") (pin "2") (pinfunction "2_2") (pintype "passive"))
      (node (ref "X1") (pin "GND1") (pinfunction "GND1_GND1") (pintype "power_in"))
      (node (ref "X1") (pin "GND2") (pinfunction "GND2_GND2") (pintype "power_in"))
      (node (ref "X1") (pin "GND3") (pinfunction "GND3_GND3") (pintype "power_in"))
      (node (ref "X1") (pin "GND4") (pinfunction "GND4_GND4") (pintype "power_in"))
      (node (ref "X2") (pin "1") (pinfunction "S_1") (pintype "passive"))
      (node (ref "Y1") (pin "2") (pinfunction "GND_2") (pintype "power_in"))
      (node (ref "Y1") (pin "4") (pinfunction "GND_4") (pintype "power_in"))
    )
    (net (code "13") (name "HT") (class "Default")
      (node (ref "U15") (pin "4") (pinfunction "HT_4") (pintype "bidirectional"))
    )
    (net (code "14") (name "HT2") (class "Default")
      (node (ref "U16") (pin "4") (pinfunction "HT_4") (pintype "bidirectional"))
    )
    (net (code "15") (name "LED") (class "Default")
      (node (ref "D1") (pin "A") (pinfunction "A_A") (pintype "passive"))
      (node (ref "U2") (pin "18") (pinfunction "PB0_18") (pintype "bidirectional"))
    )
    (net (code "16") (name "LED2") (class "Default")
      (node (ref "D2") (pin "A") (pinfunction "A_A") (pintype "passive"))
      (node (ref "U2") (pin "17") (pinfunction "PA7_17") (pintype "bidirectional"))
    )
    (net (code "17") (name "M0") (class "Default")
      (node (ref "U14") (pin "M0") (pinfunction "M0_M0") (pintype "bidirectional"))
      (node (ref "U2") (pin "10") (pinfunction "PA0-WKUP_10") (pintype "bidirectional"))
    )
    (net (code "18") (name "M1") (class "Default")
      (node (ref "U14") (pin "M1") (pinfunction "M1_M1") (pintype "bidirectional"))
      (node (ref "U2") (pin "11") (pinfunction "PA1_11") (pintype "bidirectional"))
    )
    (net (code "19") (name "MISO") (class "Default")
      (node (ref "J2") (pin "7") (pinfunction "DAT0(DO)_7") (pintype "bidirectional"))
      (node (ref "U2") (pin "27") (pinfunction "PB14_27") (pintype "bidirectional"))
    )
    (net (code "20") (name "MOSI") (class "Default")
      (node (ref "J2") (pin "3") (pinfunction "CMD(DI)_3") (pintype "bidirectional"))
      (node (ref "U2") (pin "28") (pinfunction "PB15_28") (pintype "bidirectional"))
    )
    (net (code "21") (name "NRST") (class "Default")
      (node (ref "C23") (pin "1") (pinfunction "1_1") (pintype "passive"))
      (node (ref "U2") (pin "7") (pinfunction "NRST_7") (pintype "bidirectional"))
    )
    (net (code "22") (name "Net-(D1-PadC)") (class "Default")
      (node (ref "D1") (pin "C") (pinfunction "C_C") (pintype "passive"))
      (node (ref "R1") (pin "2") (pinfunction "2_2") (pintype "passive"))
    )
    (net (code "23") (name "Net-(D2-PadC)") (class "Default")
      (node (ref "D2") (pin "C") (pinfunction "C_C") (pintype "passive"))
      (node (ref "R3") (pin "2") (pinfunction "2_2") (pintype "passive"))
    )
    (net (code "24") (name "Net-(D10-C)") (class "Default")
      (node (ref "C11") (pin "1") (pinfunction "1_1") (pintype "passive"))
      (node (ref "C2") (pin "+") (pinfunction "+_+") (pintype "passive"))
      (node (ref "D10") (pin "1") (pinfunction "C_1") (pintype "passive"))
      (node (ref "U15") (pin "3") (pinfunction "VIN_3") (pintype "input"))
    )
    (net (code "25") (name "Net-(D11-C)") (class "Default")
      (node (ref "C4") (pin "+") (pinfunction "+_+") (pintype "passive"))
      (node (ref "C9") (pin "1") (pinfunction "1_1") (pintype "passive"))
      (node (ref "D11") (pin "1") (pinfunction "C_1") (pintype "passive"))
      (node (ref "U16") (pin "3") (pinfunction "VIN_3") (pintype "input"))
    )
    (net (code "26") (name "Net-(D12-PadC)") (class "Default")
      (node (ref "D12") (pin "C") (pinfunction "C_C") (pintype "passive"))
      (node (ref "R39") (pin "2") (pinfunction "2_2") (pintype "passive"))
    )
    (net (code "27") (name "Net-(D13-PadA)") (class "Default")
      (node (ref "D13") (pin "A") (pinfunction "A_A") (pintype "passive"))
      (node (ref "R14") (pin "1") (pinfunction "1_1") (pintype "passive"))
    )
    (net (code "28") (name "Net-(D14-PadC)") (class "Default")
      (node (ref "D14") (pin "C") (pinfunction "C_C") (pintype "passive"))
      (node (ref "R18") (pin "2") (pinfunction "2_2") (pintype "passive"))
    )
    (net (code "29") (name "Net-(D15-PadC)") (class "Default")
      (node (ref "D15") (pin "C") (pinfunction "C_C") (pintype "passive"))
      (node (ref "R19") (pin "2") (pinfunction "2_2") (pintype "passive"))
    )
    (net (code "30") (name "Net-(D16-PadA)") (class "Default")
      (node (ref "D16") (pin "A") (pinfunction "A_A") (pintype "passive"))
      (node (ref "R13") (pin "1") (pinfunction "1_1") (pintype "passive"))
    )
    (net (code "31") (name "Net-(D17-PadA)") (class "Default")
      (node (ref "D17") (pin "A") (pinfunction "A_A") (pintype "passive"))
      (node (ref "R20") (pin "1") (pinfunction "1_1") (pintype "passive"))
    )
    (net (code "32") (name "Net-(DRM3-PadA)") (class "Default")
      (node (ref "DRM3") (pin "A") (pinfunction "A_A") (pintype "passive"))
      (node (ref "U1") (pin "IND") (pinfunction "IND_IND") (pintype "bidirectional"))
    )
    (net (code "33") (name "Net-(DRM3-PadC)") (class "Default")
      (node (ref "DRM3") (pin "C") (pinfunction "C_C") (pintype "passive"))
      (node (ref "R42") (pin "1") (pinfunction "1_1") (pintype "passive"))
    )
    (net (code "34") (name "Net-(J4-SIGNAL)") (class "Default")
      (node (ref "C16") (pin "1") (pinfunction "1_1") (pintype "passive"))
      (node (ref "J4") (pin "FEED") (pinfunction "SIGNAL_FEED") (pintype "bidirectional"))
      (node (ref "R4") (pin "1") (pinfunction "1_1") (pintype "passive"))
    )
    (net (code "35") (name "Net-(LS2-PadP)") (class "Default")
      (node (ref "LS2") (pin "P") (pinfunction "P_P") (pintype "passive"))
      (node (ref "R32") (pin "2") (pinfunction "2_2") (pintype "passive"))
    )
    (net (code "36") (name "Net-(POWER-Pad1)") (class "Default")
      (node (ref "POWER") (pin "1") (pinfunction "1_1") (pintype "passive"))
      (node (ref "SW2") (pin "2") (pinfunction "2_2") (pintype "passive"))
    )
    (net (code "37") (name "Net-(R8-Pad2)") (class "Default")
      (node (ref "R8") (pin "2") (pinfunction "2_2") (pintype "passive"))
      (node (ref "S2") (pin "5") (pinfunction "5_5") (pintype "passive"))
    )
    (net (code "38") (name "Net-(R9-Pad2)") (class "Default")
      (node (ref "R9") (pin "2") (pinfunction "2_2") (pintype "passive"))
      (node (ref "S2") (pin "6") (pinfunction "6_6") (pintype "passive"))
    )
    (net (code "39") (name "Net-(U13-1PPS)") (class "Default")
      (node (ref "R14") (pin "2") (pinfunction "2_2") (pintype "passive"))
      (node (ref "U13") (pin "6") (pinfunction "1PPS_6") (pintype "output"))
    )
    (net (code "40") (name "Net-(U13-AADET_N)") (class "Default")
      (node (ref "R13") (pin "2") (pinfunction "2_2") (pintype "passive"))
      (node (ref "U13") (pin "8") (pinfunction "AADET_N_8") (pintype "output"))
    )
    (net (code "41") (name "Net-(U13-FORCE_ON)") (class "Default")
      (node (ref "R11") (pin "2") (pinfunction "2_2") (pintype "passive"))
      (node (ref "R12") (pin "2") (pinfunction "2_2") (pintype "passive"))
      (node (ref "U13") (pin "7") (pinfunction "FORCE_ON_7") (pintype "input"))
    )
    (net (code "42") (name "Net-(U13-~{RESET})") (class "Default")
      (node (ref "R17") (pin "1") (pinfunction "1_1") (pintype "passive"))
      (node (ref "U13") (pin "10") (pinfunction "~{RESET}_10") (pintype "input"))
    )
    (net (code "43") (name "Net-(U15-VOUT)") (class "Default")
      (node (ref "C12") (pin "1") (pinfunction "1_1") (pintype "passive"))
      (node (ref "C3") (pin "+") (pinfunction "+_+") (pintype "passive"))
      (node (ref "F2") (pin "1") (pinfunction "1_1") (pintype "bidirectional"))
      (node (ref "U15") (pin "2") (pinfunction "VOUT_2") (pintype "output"))
    )
    (net (code "44") (name "Net-(U16-VOUT)") (class "Default")
      (node (ref "C10") (pin "1") (pinfunction "1_1") (pintype "passive"))
      (node (ref "C5") (pin "+") (pinfunction "+_+") (pintype "passive"))
      (node (ref "F4") (pin "1") (pinfunction "1_1") (pintype "bidirectional"))
      (node (ref "U16") (pin "2") (pinfunction "VOUT_2") (pintype "output"))
    )
    (net (code "45") (name "Net-(X1-ANT)") (class "Default")
      (node (ref "U14") (pin "ANT") (pinfunction "ANT_ANT") (pintype "bidirectional"))
      (node (ref "X1") (pin "ANTENNA") (pinfunction "ANT_ANTENNA") (pintype "bidirectional"))
    )
    (net (code "46") (name "OSC_IN") (class "Default")
      (node (ref "C15") (pin "2") (pinfunction "2_2") (pintype "passive"))
      (node (ref "U2") (pin "5") (pinfunction "OSC_IN_5") (pintype "input"))
      (node (ref "Y1") (pin "1") (pinfunction "1_1") (pintype "passive"))
    )
    (net (code "47") (name "OSC_OUT") (class "Default")
      (node (ref "C14") (pin "2") (pinfunction "2_2") (pintype "passive"))
      (node (ref "U2") (pin "6") (pinfunction "OSC_OUT_6") (pintype "output"))
      (node (ref "Y1") (pin "3") (pinfunction "3_3") (pintype "passive"))
    )
    (net (code "48") (name "RX1") (class "Default")
      (node (ref "U13") (pin "2") (pinfunction "TXD1_2") (pintype "output"))
      (node (ref "U2") (pin "31") (pinfunction "PA10_31") (pintype "bidirectional"))
    )
    (net (code "49") (name "RX2") (class "Default")
      (node (ref "U14") (pin "TX") (pinfunction "TXD_TX") (pintype "bidirectional"))
      (node (ref "U2") (pin "13") (pinfunction "PA3_13") (pintype "bidirectional"))
    )
    (net (code "50") (name "RX3") (class "Default")
      (node (ref "S2") (pin "8") (pinfunction "8_8") (pintype "passive"))
      (node (ref "U2") (pin "22") (pinfunction "PB11_22") (pintype "bidirectional"))
      (node (ref "X2") (pin "3") (pinfunction "S_3") (pintype "passive"))
    )
    (net (code "51") (name "RX3D") (class "Default")
      (node (ref "S2") (pin "1") (pinfunction "1_1") (pintype "passive"))
      (node (ref "U1") (pin "TX") (pinfunction "TX_TX") (pintype "bidirectional"))
    )
    (net (code "52") (name "SCK") (class "Default")
      (node (ref "J2") (pin "5") (pinfunction "CLK(SCK)_5") (pintype "bidirectional"))
      (node (ref "U2") (pin "26") (pinfunction "PB13_26") (pintype "bidirectional"))
    )
    (net (code "53") (name "SCL") (class "Default")
      (node (ref "J3") (pin "3") (pinfunction "3_3") (pintype "passive"))
      (node (ref "U2") (pin "42") (pinfunction "PB6_42") (pintype "bidirectional"))
    )
    (net (code "54") (name "SDA") (class "Default")
      (node (ref "J3") (pin "2") (pinfunction "2_2") (pintype "passive"))
      (node (ref "U2") (pin "43") (pinfunction "PB7_43") (pintype "bidirectional"))
    )
    (net (code "55") (name "SWCLK") (class "Default")
      (node (ref "STM1") (pin "2") (pinfunction "2_2") (pintype "passive"))
      (node (ref "U2") (pin "37") (pinfunction "PA14_37") (pintype "bidirectional"))
    )
    (net (code "56") (name "SWDIO") (class "Default")
      (node (ref "STM1") (pin "3") (pinfunction "3_3") (pintype "passive"))
      (node (ref "U2") (pin "34") (pinfunction "PA13_34") (pintype "bidirectional"))
    )
    (net (code "57") (name "TX1") (class "Default")
      (node (ref "R15") (pin "1") (pinfunction "1_1") (pintype "passive"))
      (node (ref "U2") (pin "30") (pinfunction "PA9_30") (pintype "bidirectional"))
    )
    (net (code "58") (name "TX2") (class "Default")
      (node (ref "U14") (pin "RX") (pinfunction "RXD_RX") (pintype "bidirectional"))
      (node (ref "U2") (pin "12") (pinfunction "PA2_12") (pintype "bidirectional"))
    )
    (net (code "59") (name "TX3") (class "Default")
      (node (ref "S2") (pin "7") (pinfunction "7_7") (pintype "passive"))
      (node (ref "U2") (pin "21") (pinfunction "PB10_21") (pintype "bidirectional"))
      (node (ref "X2") (pin "2") (pinfunction "S_2") (pintype "passive"))
    )
    (net (code "60") (name "TX3D") (class "Default")
      (node (ref "S2") (pin "2") (pinfunction "2_2") (pintype "passive"))
      (node (ref "U1") (pin "RX") (pinfunction "RX_RX") (pintype "bidirectional"))
    )
    (net (code "61") (name "TXD") (class "Default")
      (node (ref "R15") (pin "2") (pinfunction "2_2") (pintype "passive"))
      (node (ref "R16") (pin "2") (pinfunction "2_2") (pintype "passive"))
      (node (ref "U13") (pin "1") (pinfunction "RXD1_1") (pintype "input"))
    )
    (net (code "62") (name "UART-PD") (class "Default")
      (node (ref "R43") (pin "1") (pinfunction "1_1") (pintype "passive"))
      (node (ref "U1") (pin "UART-PD") (pinfunction "UART-PD_UART-PD") (pintype "bidirectional"))
      (node (ref "U2") (pin "20") (pinfunction "PB2_20") (pintype "bidirectional"))
    )
    (net (code "63") (name "USB_N") (class "Default")
      (node (ref "J5") (pin "D-1") (pinfunction "D-_D-1") (pintype "bidirectional"))
      (node (ref "U2") (pin "32") (pinfunction "PA11_32") (pintype "bidirectional"))
    )
    (net (code "64") (name "USB_P") (class "Default")
      (node (ref "J5") (pin "D+1") (pinfunction "D+_D+1") (pintype "bidirectional"))
      (node (ref "U2") (pin "33") (pinfunction "PA12_33") (pintype "bidirectional"))
    )
    (net (code "65") (name "VB") (class "Default")
      (node (ref "U2") (pin "16") (pinfunction "PA6_16") (pintype "bidirectional"))
      (node (ref "VBAT_D") (pin "2") (pinfunction "2_2") (pintype "passive"))
      (node (ref "VBAT_U") (pin "1") (pinfunction "1_1") (pintype "passive"))
    )
    (net (code "66") (name "VCC") (class "Default")
      (node (ref "D10") (pin "2") (pinfunction "A_2") (pintype "passive"))
      (node (ref "D11") (pin "2") (pinfunction "A_2") (pintype "passive"))
      (node (ref "D3") (pin "1") (pinfunction "C_1") (pintype "passive"))
      (node (ref "SW2") (pin "1") (pinfunction "1_1") (pintype "passive"))
      (node (ref "VBAT_U") (pin "2") (pinfunction "2_2") (pintype "passive"))
    )
    (net (code "67") (name "VDDA") (class "Default")
      (node (ref "L2") (pin "2") (pinfunction "2_2") (pintype "passive"))
      (node (ref "U2") (pin "9") (pinfunction "VDDA_9") (pintype "power_in"))
      (node (ref "VDDA3") (pin "1") (pinfunction "1_1") (pintype "passive"))
      (node (ref "VDDA4") (pin "1") (pinfunction "1_1") (pintype "passive"))
    )
    (net (code "68") (name "V_BCKP") (class "Default")
      (node (ref "B1") (pin "+") (pinfunction "+_+") (pintype "power_in"))
      (node (ref "C24") (pin "1") (pinfunction "1_1") (pintype "passive"))
      (node (ref "C26") (pin "+") (pinfunction "+_+") (pintype "passive"))
      (node (ref "R39") (pin "1") (pinfunction "1_1") (pintype "passive"))
      (node (ref "U13") (pin "5") (pinfunction "V_BCKP_5") (pintype "power_in"))
    )
    (net (code "69") (name "XANT") (class "Default")
      (node (ref "C17") (pin "1") (pinfunction "1_1") (pintype "passive"))
      (node (ref "R4") (pin "2") (pinfunction "2_2") (pintype "passive"))
      (node (ref "U13") (pin "11") (pinfunction "EX_ANT_11") (pintype "input"))
    )
    (net (code "70") (name "unconnected-(J2B-DAT1(RSV)-Pad8)") (class "Default")
      (node (ref "J2") (pin "8") (pinfunction "DAT1(RSV)_8") (pintype "bidirectional"))
    )
    (net (code "71") (name "unconnected-(J2B-DAT2(NC)-Pad1)") (class "Default")
      (node (ref "J2") (pin "1") (pinfunction "DAT2(NC)_1") (pintype "bidirectional"))
    )
    (net (code "72") (name "unconnected-(J5-USBID-PadID1)") (class "Default")
      (node (ref "J5") (pin "ID1") (pinfunction "USBID_ID1") (pintype "bidirectional"))
    )
    (net (code "73") (name "unconnected-(U1-PadADC)") (class "Default")
      (node (ref "U1") (pin "ADC") (pinfunction "ADC_ADC") (pintype "bidirectional"))
    )
    (net (code "74") (name "unconnected-(U1-PadCTS)") (class "Default")
      (node (ref "U1") (pin "CTS") (pinfunction "CTS_CTS") (pintype "bidirectional"))
    )
    (net (code "75") (name "unconnected-(U1-PadDCC)") (class "Default")
      (node (ref "U1") (pin "DCC") (pinfunction "DCC_DCC") (pintype "bidirectional"))
    )
    (net (code "76") (name "unconnected-(U1-PadDEC4)") (class "Default")
      (node (ref "U1") (pin "DEC4") (pinfunction "DEC4_DEC4") (pintype "bidirectional"))
    )
    (net (code "77") (name "unconnected-(U1-PadRESET)") (class "Default")
      (node (ref "U1") (pin "RESET") (pinfunction "RESET_RESET") (pintype "bidirectional"))
    )
    (net (code "78") (name "unconnected-(U1-PadRTS)") (class "Default")
      (node (ref "U1") (pin "RTS") (pinfunction "RTS_RTS") (pintype "bidirectional"))
    )
    (net (code "79") (name "unconnected-(U2A-PA4-Pad14)") (class "Default")
      (node (ref "U2") (pin "14") (pinfunction "PA4_14") (pintype "bidirectional"))
    )
    (net (code "80") (name "unconnected-(U2A-PA15-Pad38)") (class "Default")
      (node (ref "U2") (pin "38") (pinfunction "PA15_38") (pintype "bidirectional"))
    )
    (net (code "81") (name "unconnected-(U2A-PB3-Pad39)") (class "Default")
      (node (ref "U2") (pin "39") (pinfunction "PB3_39") (pintype "bidirectional"))
    )
    (net (code "82") (name "unconnected-(U2A-PC13-Pad2)") (class "Default")
      (node (ref "U2") (pin "2") (pinfunction "PC13_2") (pintype "bidirectional"))
    )
    (net (code "83") (name "unconnected-(U2A-PC14-OSC32_IN-Pad3)") (class "Default")
      (node (ref "U2") (pin "3") (pinfunction "PC14-OSC32_IN_3") (pintype "bidirectional"))
    )
    (net (code "84") (name "unconnected-(U2A-PC15-OSC32_OUT-Pad4)") (class "Default")
      (node (ref "U2") (pin "4") (pinfunction "PC15-OSC32_OUT_4") (pintype "bidirectional"))
    )
    (net (code "85") (name "unconnected-(U14-Pad3V3)") (class "Default")
      (node (ref "U14") (pin "3V3") (pinfunction "3V3_3V3") (pintype "bidirectional"))
    )
    (net (code "86") (name "unconnected-(U14-PadPB0)") (class "Default")
      (node (ref "U14") (pin "PB0") (pinfunction "PB0_PB0") (pintype "bidirectional"))
    )
    (net (code "87") (name "unconnected-(U14-PadPB1)") (class "Default")
      (node (ref "U14") (pin "PB1") (pinfunction "PB1_PB1") (pintype "bidirectional"))
    )
    (net (code "88") (name "unconnected-(U14-PadPB3)") (class "Default")
      (node (ref "U14") (pin "PB3") (pinfunction "PB3_PB3") (pintype "bidirectional"))
    )
    (net (code "89") (name "unconnected-(U14-PadRST)") (class "Default")
      (node (ref "U14") (pin "RST") (pinfunction "RST_RST") (pintype "bidirectional"))
    )
    (net (code "90") (name "unconnected-(U14-PadSWIM)") (class "Default")
      (node (ref "U14") (pin "SWIM") (pinfunction "SWIM_SWIM") (pintype "bidirectional"))
    )
  )
)
